# Modul_PCB_lama.net
KiCad netlist of a schematic drawn in EAGLE
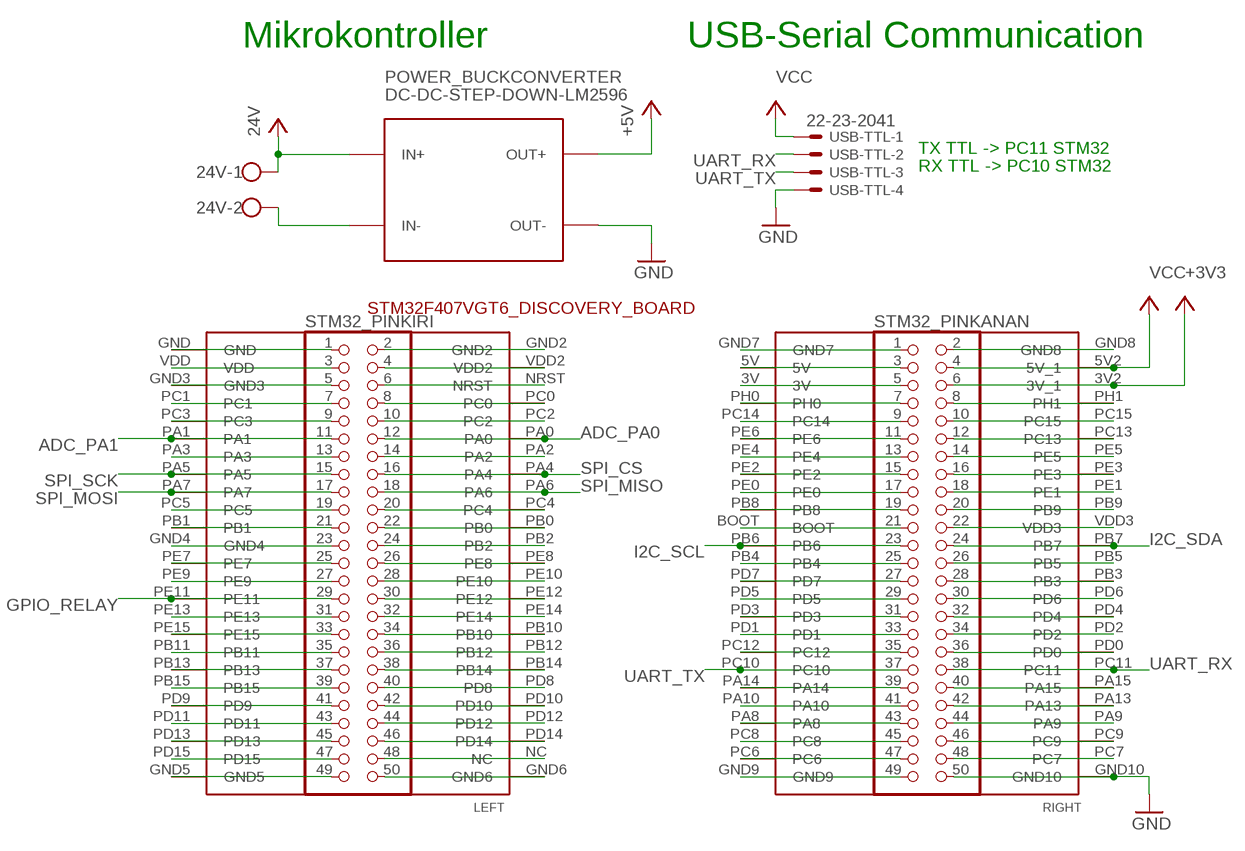
[diagram p0: schematic, sheet 1, part 1 of 2]
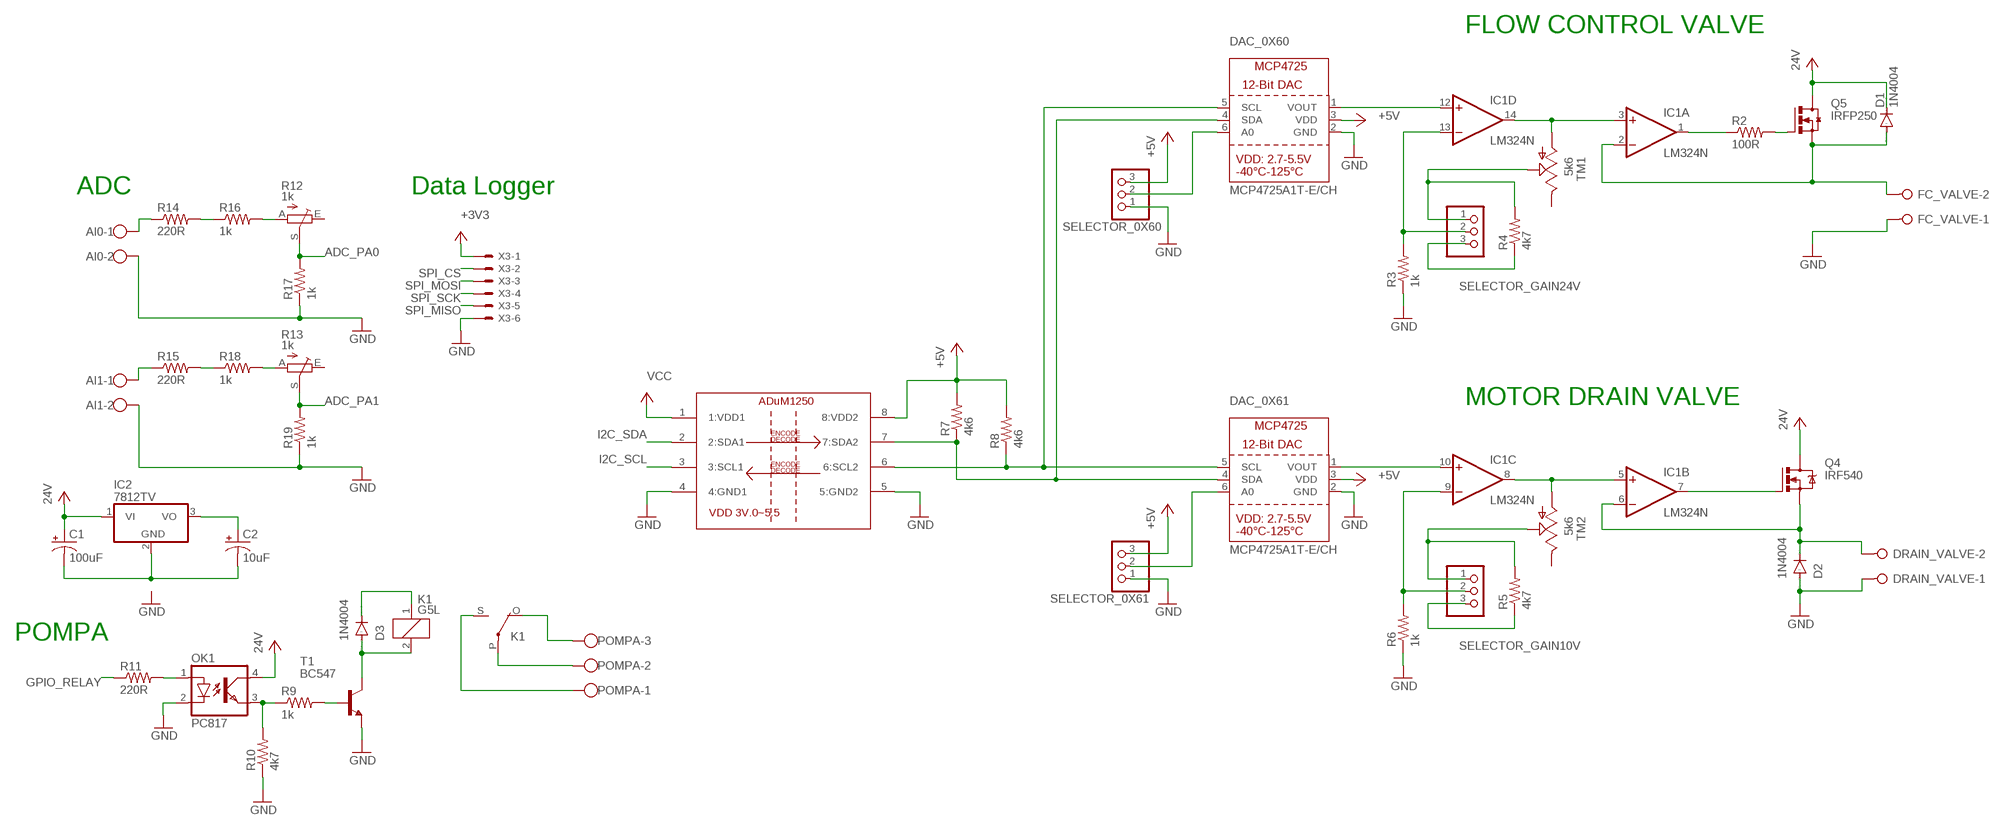
[diagram p1: schematic, sheet 1, part 2 of 2]

(export (version "E")
  (design (tool "Eeschema 10.0.6"))
  (components
    (comp (ref "24V")
      (value "W237-102")
      (footprint "eagle-import:W237-102")
      (fields (field (name "MPN") "237-102"))
      (libsource (lib "eagle-import") (part "W237-102"))
    )
    (comp (ref "AI0")
      (value "W237-102")
      (footprint "eagle-import:W237-102")
      (fields (field (name "MPN") "237-102"))
      (libsource (lib "eagle-import") (part "W237-102"))
    )
    (comp (ref "AI1")
      (value "W237-102")
      (footprint "eagle-import:W237-102")
      (fields (field (name "MPN") "237-102"))
      (libsource (lib "eagle-import") (part "W237-102"))
    )
    (comp (ref "C1")
      (value "100uF")
      (footprint "eagle-import:E2,5-6")
      (libsource (lib "eagle-import") (part "CPOL-USE2.5-6"))
    )
    (comp (ref "C2")
      (value "10uF")
      (footprint "eagle-import:E2,5-6")
      (libsource (lib "eagle-import") (part "CPOL-USE2.5-6"))
    )
    (comp (ref "D1")
      (value "1N4004")
      (footprint "eagle-import:DO41-10")
      (libsource (lib "eagle-import") (part "1N4004"))
    )
    (comp (ref "D2")
      (value "1N4004")
      (footprint "eagle-import:DO41-10")
      (libsource (lib "eagle-import") (part "1N4004"))
    )
    (comp (ref "D3")
      (value "1N4004")
      (footprint "eagle-import:DO41-10")
      (libsource (lib "eagle-import") (part "1N4004"))
    )
    (comp (ref "DAC_0X60")
      (value "MCP4725A1T-E/CH")
      (footprint "eagle-import:SOT23-6")
      (libsource (lib "eagle-import") (part "DAC_MCP4725"))
    )
    (comp (ref "DAC_0X61")
      (value "MCP4725A1T-E/CH")
      (footprint "eagle-import:SOT23-6")
      (libsource (lib "eagle-import") (part "DAC_MCP4725"))
    )
    (comp (ref "DRAIN_VALVE")
      (value "W237-02P")
      (footprint "eagle-import:W237-132")
      (libsource (lib "eagle-import") (part "W237-02P"))
    )
    (comp (ref "FC_VALVE")
      (value "W237-02P")
      (footprint "eagle-import:W237-132")
      (libsource (lib "eagle-import") (part "W237-02P"))
    )
    (comp (ref "IC1")
      (value "LM324N")
      (footprint "eagle-import:DIL14")
      (libsource (lib "eagle-import") (part "LM324N"))
    )
    (comp (ref "IC2")
      (value "7812TV")
      (footprint "eagle-import:TO220V")
      (libsource (lib "eagle-import") (part "78TV12"))
    )
    (comp (ref "K1")
      (value "G5L")
      (footprint "eagle-import:G5LE")
      (libsource (lib "eagle-import") (part "G5L"))
    )
    (comp (ref "OK1")
      (value "PC817")
      (footprint "eagle-import:DIL04")
      (fields (field (name "MPN") "PC817X4J000F"))
      (libsource (lib "eagle-import") (part "PC817"))
    )
    (comp (ref "POMPA")
      (value "W237-103")
      (footprint "eagle-import:W237-103")
      (fields (field (name "MPN") "237-103"))
      (libsource (lib "eagle-import") (part "W237-103"))
    )
    (comp (ref "POWER_BUCKCONVERTER")
      (value "DC-DC-STEP-DOWN-LM2596")
      (footprint "eagle-import:DC-DC-STEP-DOWN-LM2596")
      (libsource (lib "eagle-import") (part "DC-DC-STEP-DOWN-LM2596"))
    )
    (comp (ref "Q4")
      (value "IRF540")
      (footprint "eagle-import:TO220BV")
      (libsource (lib "eagle-import") (part "IRF540"))
    )
    (comp (ref "Q5")
      (value "IRFP250")
      (footprint "eagle-import:TO-247AD-V")
      (libsource (lib "eagle-import") (part "IRFP250"))
    )
    (comp (ref "R2")
      (value "100R")
      (footprint "eagle-import:0207_10")
      (libsource (lib "eagle-import") (part "R-US_0207/10"))
    )
    (comp (ref "R3")
      (value "1k")
      (footprint "eagle-import:0207_10")
      (libsource (lib "eagle-import") (part "R-US_0207/10"))
    )
    (comp (ref "R4")
      (value "4k7")
      (footprint "eagle-import:0207_10")
      (libsource (lib "eagle-import") (part "R-US_0207/10"))
    )
    (comp (ref "R5")
      (value "4k7")
      (footprint "eagle-import:0207_10")
      (libsource (lib "eagle-import") (part "R-US_0207/10"))
    )
    (comp (ref "R6")
      (value "1k")
      (footprint "eagle-import:0207_10")
      (libsource (lib "eagle-import") (part "R-US_0207/10"))
    )
    (comp (ref "R7")
      (value "4k6")
      (footprint "eagle-import:0207_10")
      (libsource (lib "eagle-import") (part "R-US_0207/10"))
    )
    (comp (ref "R8")
      (value "4k6")
      (footprint "eagle-import:0207_10")
      (libsource (lib "eagle-import") (part "R-US_0207/10"))
    )
    (comp (ref "R9")
      (value "1k")
      (footprint "eagle-import:0207_10")
      (libsource (lib "eagle-import") (part "R-US_0207/10"))
    )
    (comp (ref "R10")
      (value "4k7")
      (footprint "eagle-import:0207_10")
      (libsource (lib "eagle-import") (part "R-US_0207/10"))
    )
    (comp (ref "R11")
      (value "220R")
      (footprint "eagle-import:0207_10")
      (libsource (lib "eagle-import") (part "R-US_0207/10"))
    )
    (comp (ref "R12")
      (value "1k")
      (footprint "eagle-import:RJ9W")
      (libsource (lib "eagle-import") (part "TRIM_EU-RJ9W"))
    )
    (comp (ref "R13")
      (value "1k")
      (footprint "eagle-import:RJ9W")
      (libsource (lib "eagle-import") (part "TRIM_EU-RJ9W"))
    )
    (comp (ref "R14")
      (value "220R")
      (footprint "eagle-import:0207_10")
      (libsource (lib "eagle-import") (part "R-US_0207/10"))
    )
    (comp (ref "R15")
      (value "220R")
      (footprint "eagle-import:0207_10")
      (libsource (lib "eagle-import") (part "R-US_0207/10"))
    )
    (comp (ref "R16")
      (value "1k")
      (footprint "eagle-import:0207_10")
      (libsource (lib "eagle-import") (part "R-US_0207/10"))
    )
    (comp (ref "R17")
      (value "1k")
      (footprint "eagle-import:0207_10")
      (libsource (lib "eagle-import") (part "R-US_0207/10"))
    )
    (comp (ref "R18")
      (value "1k")
      (footprint "eagle-import:0207_10")
      (libsource (lib "eagle-import") (part "R-US_0207/10"))
    )
    (comp (ref "R19")
      (value "1k")
      (footprint "eagle-import:0207_10")
      (libsource (lib "eagle-import") (part "R-US_0207/10"))
    )
    (comp (ref "SELECTOR_0X60")
      (value "PINHD-1X3")
      (footprint "eagle-import:1X03")
      (libsource (lib "eagle-import") (part "PINHD-1X3"))
    )
    (comp (ref "SELECTOR_0X61")
      (value "PINHD-1X3")
      (footprint "eagle-import:1X03")
      (libsource (lib "eagle-import") (part "PINHD-1X3"))
    )
    (comp (ref "SELECTOR_GAIN10V")
      (value "PINHD-1X3")
      (footprint "eagle-import:1X03")
      (libsource (lib "eagle-import") (part "PINHD-1X3"))
    )
    (comp (ref "SELECTOR_GAIN24V")
      (value "PINHD-1X3")
      (footprint "eagle-import:1X03")
      (libsource (lib "eagle-import") (part "PINHD-1X3"))
    )
    (comp (ref "STM32F407VGT6_DISCOVERY_BOARD")
      (value "STM32F4-DISCOVERY")
      (footprint "eagle-import:STM32F407VG")
      (libsource (lib "eagle-import") (part "STM32F4-DISCOVERY"))
    )
    (comp (ref "STM32_PINKANAN")
      (value "PINHD-2X25")
      (footprint "eagle-import:2X25")
      (libsource (lib "eagle-import") (part "PINHD-2X25"))
    )
    (comp (ref "STM32_PINKIRI")
      (value "PINHD-2X25")
      (footprint "eagle-import:2X25")
      (libsource (lib "eagle-import") (part "PINHD-2X25"))
    )
    (comp (ref "T1")
      (value "BC547")
      (footprint "eagle-import:TO92")
      (libsource (lib "eagle-import") (part "BC547"))
    )
    (comp (ref "TM1")
      (value "5k6")
      (footprint "eagle-import:6MM")
      (libsource (lib "eagle-import") (part "TRIM"))
    )
    (comp (ref "TM2")
      (value "5k6")
      (footprint "eagle-import:6MM")
      (libsource (lib "eagle-import") (part "TRIM"))
    )
    (comp (ref "U$1")
      (value "ADUM1250")
      (footprint "eagle-import:SOIC_N")
      (libsource (lib "eagle-import") (part "ADUM1250"))
    )
    (comp (ref "USB-TTL")
      (value "22-23-2041")
      (footprint "eagle-import:22-23-2041")
      (fields (field (name "MF") "MOLEX"))
      (libsource (lib "eagle-import") (part "22-23-2041"))
    )
    (comp (ref "X3")
      (value "22-23-2061")
      (footprint "eagle-import:22-23-2061")
      (fields (field (name "MF") "MOLEX"))
      (libsource (lib "eagle-import") (part "22-23-2061"))
    )
  )
  (nets
    (net (code "1") (name "+3V3") (class "Default")
      (node (ref "STM32F407VGT6_DISCOVERY_BOARD") (pin "3V2") (pinfunction "3V_1_3V2") (pintype "bidirectional"))
      (node (ref "STM32_PINKANAN") (pin "6") (pinfunction "6_6") (pintype "passive"))
      (node (ref "X3") (pin "1") (pinfunction "S_1") (pintype "passive"))
    )
    (net (code "2") (name "+5V") (class "Default")
      (node (ref "DAC_0X60") (pin "3") (pinfunction "VDD_3") (pintype "power_in"))
      (node (ref "DAC_0X61") (pin "3") (pinfunction "VDD_3") (pintype "power_in"))
      (node (ref "POWER_BUCKCONVERTER") (pin "OUT+") (pinfunction "OUT+_OUT+") (pintype "bidirectional"))
      (node (ref "R7") (pin "2") (pinfunction "2_2") (pintype "passive"))
      (node (ref "R8") (pin "2") (pinfunction "2_2") (pintype "passive"))
      (node (ref "SELECTOR_0X60") (pin "3") (pinfunction "3_3") (pintype "passive"))
      (node (ref "SELECTOR_0X61") (pin "3") (pinfunction "3_3") (pintype "passive"))
      (node (ref "U$1") (pin "8") (pinfunction "8:VDD2_8") (pintype "bidirectional"))
    )
    (net (code "3") (name "/ADC_PA0") (class "Default")
      (node (ref "R12") (pin "S") (pinfunction "S_S") (pintype "passive"))
      (node (ref "R17") (pin "2") (pinfunction "2_2") (pintype "passive"))
      (node (ref "STM32F407VGT6_DISCOVERY_BOARD") (pin "PA0") (pinfunction "PA0_PA0") (pintype "bidirectional"))
      (node (ref "STM32_PINKIRI") (pin "12") (pinfunction "12_12") (pintype "passive"))
    )
    (net (code "4") (name "/ADC_PA1") (class "Default")
      (node (ref "R13") (pin "S") (pinfunction "S_S") (pintype "passive"))
      (node (ref "R19") (pin "2") (pinfunction "2_2") (pintype "passive"))
      (node (ref "STM32F407VGT6_DISCOVERY_BOARD") (pin "PA1") (pinfunction "PA1_PA1") (pintype "bidirectional"))
      (node (ref "STM32_PINKIRI") (pin "11") (pinfunction "11_11") (pintype "passive"))
    )
    (net (code "5") (name "/GPIO_RELAY") (class "Default")
      (node (ref "R11") (pin "1") (pinfunction "1_1") (pintype "passive"))
      (node (ref "STM32F407VGT6_DISCOVERY_BOARD") (pin "PE11") (pinfunction "PE11_PE11") (pintype "bidirectional"))
      (node (ref "STM32_PINKIRI") (pin "29") (pinfunction "29_29") (pintype "passive"))
    )
    (net (code "6") (name "/I2C_SCL") (class "Default")
      (node (ref "STM32F407VGT6_DISCOVERY_BOARD") (pin "PB6") (pinfunction "PB6_PB6") (pintype "bidirectional"))
      (node (ref "STM32_PINKANAN") (pin "23") (pinfunction "23_23") (pintype "passive"))
      (node (ref "U$1") (pin "3") (pinfunction "3:SCL1_3") (pintype "bidirectional"))
    )
    (net (code "7") (name "/I2C_SDA") (class "Default")
      (node (ref "STM32F407VGT6_DISCOVERY_BOARD") (pin "PB7") (pinfunction "PB7_PB7") (pintype "bidirectional"))
      (node (ref "STM32_PINKANAN") (pin "24") (pinfunction "24_24") (pintype "passive"))
      (node (ref "U$1") (pin "2") (pinfunction "2:SDA1_2") (pintype "bidirectional"))
    )
    (net (code "8") (name "/SPI_CS") (class "Default")
      (node (ref "STM32F407VGT6_DISCOVERY_BOARD") (pin "PA4") (pinfunction "PA4_PA4") (pintype "bidirectional"))
      (node (ref "STM32_PINKIRI") (pin "16") (pinfunction "16_16") (pintype "passive"))
      (node (ref "X3") (pin "2") (pinfunction "S_2") (pintype "passive"))
    )
    (net (code "9") (name "/SPI_MISO") (class "Default")
      (node (ref "STM32F407VGT6_DISCOVERY_BOARD") (pin "PA6") (pinfunction "PA6_PA6") (pintype "bidirectional"))
      (node (ref "STM32_PINKIRI") (pin "18") (pinfunction "18_18") (pintype "passive"))
      (node (ref "X3") (pin "5") (pinfunction "S_5") (pintype "passive"))
    )
    (net (code "10") (name "/SPI_MOSI") (class "Default")
      (node (ref "STM32F407VGT6_DISCOVERY_BOARD") (pin "PA7") (pinfunction "PA7_PA7") (pintype "bidirectional"))
      (node (ref "STM32_PINKIRI") (pin "17") (pinfunction "17_17") (pintype "passive"))
      (node (ref "X3") (pin "3") (pinfunction "S_3") (pintype "passive"))
    )
    (net (code "11") (name "/SPI_SCK") (class "Default")
      (node (ref "STM32F407VGT6_DISCOVERY_BOARD") (pin "PA5") (pinfunction "PA5_PA5") (pintype "bidirectional"))
      (node (ref "STM32_PINKIRI") (pin "15") (pinfunction "15_15") (pintype "passive"))
      (node (ref "X3") (pin "4") (pinfunction "S_4") (pintype "passive"))
    )
    (net (code "12") (name "/UART_RX") (class "Default")
      (node (ref "STM32F407VGT6_DISCOVERY_BOARD") (pin "PC11") (pinfunction "PC11_PC11") (pintype "bidirectional"))
      (node (ref "STM32_PINKANAN") (pin "38") (pinfunction "38_38") (pintype "passive"))
      (node (ref "USB-TTL") (pin "2") (pinfunction "S_2") (pintype "passive"))
    )
    (net (code "13") (name "/UART_TX") (class "Default")
      (node (ref "STM32F407VGT6_DISCOVERY_BOARD") (pin "PC10") (pinfunction "PC10_PC10") (pintype "bidirectional"))
      (node (ref "STM32_PINKANAN") (pin "37") (pinfunction "37_37") (pintype "passive"))
      (node (ref "USB-TTL") (pin "3") (pinfunction "S_3") (pintype "passive"))
    )
    (net (code "14") (name "24V") (class "Default")
      (node (ref "24V") (pin "1") (pinfunction "KL_1") (pintype "passive"))
      (node (ref "C1") (pin "+") (pinfunction "+_+") (pintype "passive"))
      (node (ref "D1") (pin "C") (pinfunction "C_C") (pintype "passive"))
      (node (ref "IC2") (pin "1") (pinfunction "VI_1") (pintype "input"))
      (node (ref "OK1") (pin "4") (pinfunction "COL_4") (pintype "passive"))
      (node (ref "POWER_BUCKCONVERTER") (pin "IN+") (pinfunction "IN+_IN+") (pintype "bidirectional"))
      (node (ref "Q4") (pin "D") (pinfunction "D_D") (pintype "passive"))
      (node (ref "Q5") (pin "D") (pinfunction "D_D") (pintype "passive"))
      (node (ref "STM32F407VGT6_DISCOVERY_BOARD") (pin "5V2") (pinfunction "5V_1_5V2") (pintype "bidirectional"))
      (node (ref "STM32_PINKANAN") (pin "4") (pinfunction "4_4") (pintype "passive"))
      (node (ref "U$1") (pin "1") (pinfunction "1:VDD1_1") (pintype "bidirectional"))
      (node (ref "USB-TTL") (pin "1") (pinfunction "S_1") (pintype "passive"))
    )
    (net (code "15") (name "GND") (class "Default")
      (node (ref "AI0") (pin "2") (pinfunction "KL_2") (pintype "passive"))
      (node (ref "AI1") (pin "2") (pinfunction "KL_2") (pintype "passive"))
      (node (ref "D2") (pin "A") (pinfunction "A_A") (pintype "passive"))
      (node (ref "DAC_0X60") (pin "2") (pinfunction "GND_2") (pintype "power_in"))
      (node (ref "DAC_0X61") (pin "2") (pinfunction "GND_2") (pintype "power_in"))
      (node (ref "DRAIN_VALVE") (pin "1") (pinfunction "KL_1") (pintype "passive"))
      (node (ref "FC_VALVE") (pin "1") (pinfunction "KL_1") (pintype "passive"))
      (node (ref "OK1") (pin "2") (pinfunction "C_2") (pintype "passive"))
      (node (ref "POWER_BUCKCONVERTER") (pin "OUT-") (pinfunction "OUT-_OUT-") (pintype "bidirectional"))
      (node (ref "R10") (pin "1") (pinfunction "1_1") (pintype "passive"))
      (node (ref "R17") (pin "1") (pinfunction "1_1") (pintype "passive"))
      (node (ref "R19") (pin "1") (pinfunction "1_1") (pintype "passive"))
      (node (ref "R3") (pin "1") (pinfunction "1_1") (pintype "passive"))
      (node (ref "R6") (pin "1") (pinfunction "1_1") (pintype "passive"))
      (node (ref "SELECTOR_0X60") (pin "1") (pinfunction "1_1") (pintype "passive"))
      (node (ref "SELECTOR_0X61") (pin "1") (pinfunction "1_1") (pintype "passive"))
      (node (ref "STM32F407VGT6_DISCOVERY_BOARD") (pin "GND10") (pinfunction "GND10_GND10") (pintype "bidirectional"))
      (node (ref "STM32_PINKANAN") (pin "50") (pinfunction "50_50") (pintype "passive"))
      (node (ref "T1") (pin "1") (pinfunction "E_1") (pintype "passive"))
      (node (ref "U$1") (pin "4") (pinfunction "4:GND1_4") (pintype "bidirectional"))
      (node (ref "U$1") (pin "5") (pinfunction "5:GND2_5") (pintype "bidirectional"))
      (node (ref "USB-TTL") (pin "4") (pinfunction "S_4") (pintype "passive"))
      (node (ref "X3") (pin "6") (pinfunction "S_6") (pintype "passive"))
    )
    (net (code "16") (name "Net-(24VB-KL)") (class "Default")
      (node (ref "24V") (pin "2") (pinfunction "KL_2") (pintype "passive"))
      (node (ref "POWER_BUCKCONVERTER") (pin "IN-") (pinfunction "IN-_IN-") (pintype "bidirectional"))
    )
    (net (code "17") (name "Net-(AI0A-KL)") (class "Default")
      (node (ref "AI0") (pin "1") (pinfunction "KL_1") (pintype "passive"))
      (node (ref "R14") (pin "1") (pinfunction "1_1") (pintype "passive"))
    )
    (net (code "18") (name "Net-(AI1A-KL)") (class "Default")
      (node (ref "AI1") (pin "1") (pinfunction "KL_1") (pintype "passive"))
      (node (ref "R15") (pin "1") (pinfunction "1_1") (pintype "passive"))
    )
    (net (code "19") (name "Net-(D3-PadC)") (class "Default")
      (node (ref "D3") (pin "C") (pinfunction "C_C") (pintype "passive"))
      (node (ref "K1") (pin "1") (pinfunction "1_1") (pintype "passive"))
    )
    (net (code "20") (name "Net-(DAC_0X60-A0)") (class "Default")
      (node (ref "DAC_0X60") (pin "6") (pinfunction "A0_6") (pintype "input"))
      (node (ref "SELECTOR_0X60") (pin "2") (pinfunction "2_2") (pintype "passive"))
    )
    (net (code "21") (name "Net-(DAC_0X60-SCL)") (class "Default")
      (node (ref "DAC_0X60") (pin "5") (pinfunction "SCL_5") (pintype "bidirectional"))
      (node (ref "DAC_0X61") (pin "5") (pinfunction "SCL_5") (pintype "bidirectional"))
      (node (ref "R8") (pin "1") (pinfunction "1_1") (pintype "passive"))
      (node (ref "U$1") (pin "6") (pinfunction "6:SCL2_6") (pintype "bidirectional"))
    )
    (net (code "22") (name "Net-(DAC_0X60-SDA)") (class "Default")
      (node (ref "DAC_0X60") (pin "4") (pinfunction "SDA_4") (pintype "bidirectional"))
      (node (ref "DAC_0X61") (pin "4") (pinfunction "SDA_4") (pintype "bidirectional"))
      (node (ref "R7") (pin "1") (pinfunction "1_1") (pintype "passive"))
      (node (ref "U$1") (pin "7") (pinfunction "7:SDA2_7") (pintype "bidirectional"))
    )
    (net (code "23") (name "Net-(DAC_0X60-VOUT)") (class "Default")
      (node (ref "DAC_0X60") (pin "1") (pinfunction "VOUT_1") (pintype "output"))
      (node (ref "IC1") (pin "12") (pinfunction "+IN_12") (pintype "input"))
    )
    (net (code "24") (name "Net-(DAC_0X61-A0)") (class "Default")
      (node (ref "DAC_0X61") (pin "6") (pinfunction "A0_6") (pintype "input"))
      (node (ref "SELECTOR_0X61") (pin "2") (pinfunction "2_2") (pintype "passive"))
    )
    (net (code "25") (name "Net-(DAC_0X61-VOUT)") (class "Default")
      (node (ref "DAC_0X61") (pin "1") (pinfunction "VOUT_1") (pintype "output"))
      (node (ref "IC1") (pin "10") (pinfunction "+IN_10") (pintype "input"))
    )
    (net (code "26") (name "Net-(DRAIN_VALVEB-KL)") (class "Default")
      (node (ref "D2") (pin "C") (pinfunction "C_C") (pintype "passive"))
      (node (ref "DRAIN_VALVE") (pin "2") (pinfunction "KL_2") (pintype "passive"))
      (node (ref "IC1") (pin "6") (pinfunction "-IN_6") (pintype "input"))
      (node (ref "Q4") (pin "S") (pinfunction "S_S") (pintype "passive"))
    )
    (net (code "27") (name "Net-(FC_VALVEB-KL)") (class "Default")
      (node (ref "D1") (pin "A") (pinfunction "A_A") (pintype "passive"))
      (node (ref "FC_VALVE") (pin "2") (pinfunction "KL_2") (pintype "passive"))
      (node (ref "IC1") (pin "2") (pinfunction "-IN_2") (pintype "input"))
      (node (ref "Q5") (pin "S") (pinfunction "S_S") (pintype "passive"))
    )
    (net (code "28") (name "Net-(IC1A-+IN)") (class "Default")
      (node (ref "IC1") (pin "14") (pinfunction "OUT_14") (pintype "output"))
      (node (ref "IC1") (pin "3") (pinfunction "+IN_3") (pintype "input"))
      (node (ref "TM1") (pin "A") (pinfunction "A_A") (pintype "passive"))
    )
    (net (code "29") (name "Net-(IC1A-OUT)") (class "Default")
      (node (ref "IC1") (pin "1") (pinfunction "OUT_1") (pintype "output"))
      (node (ref "R2") (pin "1") (pinfunction "1_1") (pintype "passive"))
    )
    (net (code "30") (name "Net-(IC1B-+IN)") (class "Default")
      (node (ref "IC1") (pin "5") (pinfunction "+IN_5") (pintype "input"))
      (node (ref "IC1") (pin "8") (pinfunction "OUT_8") (pintype "output"))
      (node (ref "TM2") (pin "A") (pinfunction "A_A") (pintype "passive"))
    )
    (net (code "31") (name "Net-(IC1B-OUT)") (class "Default")
      (node (ref "IC1") (pin "7") (pinfunction "OUT_7") (pintype "output"))
      (node (ref "Q4") (pin "G") (pinfunction "G_G") (pintype "passive"))
    )
    (net (code "32") (name "Net-(IC1C--IN)") (class "Default")
      (node (ref "IC1") (pin "9") (pinfunction "-IN_9") (pintype "input"))
      (node (ref "R6") (pin "2") (pinfunction "2_2") (pintype "passive"))
      (node (ref "SELECTOR_GAIN10V") (pin "2") (pinfunction "2_2") (pintype "passive"))
    )
    (net (code "33") (name "Net-(IC1D--IN)") (class "Default")
      (node (ref "IC1") (pin "13") (pinfunction "-IN_13") (pintype "input"))
      (node (ref "R3") (pin "2") (pinfunction "2_2") (pintype "passive"))
      (node (ref "SELECTOR_GAIN24V") (pin "2") (pinfunction "2_2") (pintype "passive"))
    )
    (net (code "34") (name "Net-(IC2-GND)") (class "Default")
      (node (ref "C1") (pin "-") (pinfunction "-_-") (pintype "passive"))
      (node (ref "C2") (pin "-") (pinfunction "-_-") (pintype "passive"))
      (node (ref "IC2") (pin "2") (pinfunction "GND_2") (pintype "passive"))
    )
    (net (code "35") (name "Net-(IC2-VO)") (class "Default")
      (node (ref "C2") (pin "+") (pinfunction "+_+") (pintype "passive"))
      (node (ref "IC2") (pin "3") (pinfunction "VO_3") (pintype "passive"))
    )
    (net (code "36") (name "Net-(OK1-A)") (class "Default")
      (node (ref "OK1") (pin "1") (pinfunction "A_1") (pintype "passive"))
      (node (ref "R11") (pin "2") (pinfunction "2_2") (pintype "passive"))
    )
    (net (code "37") (name "Net-(OK1-EMIT)") (class "Default")
      (node (ref "OK1") (pin "3") (pinfunction "EMIT_3") (pintype "passive"))
      (node (ref "R10") (pin "2") (pinfunction "2_2") (pintype "passive"))
      (node (ref "R9") (pin "1") (pinfunction "1_1") (pintype "passive"))
    )
    (net (code "38") (name "Net-(POMPAA-KL)") (class "Default")
      (node (ref "K1") (pin "S") (pinfunction "S_S") (pintype "passive"))
      (node (ref "POMPA") (pin "1") (pinfunction "KL_1") (pintype "passive"))
    )
    (net (code "39") (name "Net-(POMPAB-KL)") (class "Default")
      (node (ref "K1") (pin "P") (pinfunction "P_P") (pintype "passive"))
      (node (ref "POMPA") (pin "2") (pinfunction "KL_2") (pintype "passive"))
    )
    (net (code "40") (name "Net-(POMPAC-KL)") (class "Default")
      (node (ref "K1") (pin "O") (pinfunction "O_O") (pintype "passive"))
      (node (ref "POMPA") (pin "3") (pinfunction "KL_3") (pintype "passive"))
    )
    (net (code "41") (name "Net-(Q5-PadG)") (class "Default")
      (node (ref "Q5") (pin "G") (pinfunction "G_G") (pintype "passive"))
      (node (ref "R2") (pin "2") (pinfunction "2_2") (pintype "passive"))
    )
    (net (code "42") (name "Net-(R4-Pad1)") (class "Default")
      (node (ref "R4") (pin "1") (pinfunction "1_1") (pintype "passive"))
      (node (ref "SELECTOR_GAIN24V") (pin "3") (pinfunction "3_3") (pintype "passive"))
    )
    (net (code "43") (name "Net-(R4-Pad2)") (class "Default")
      (node (ref "R4") (pin "2") (pinfunction "2_2") (pintype "passive"))
      (node (ref "SELECTOR_GAIN24V") (pin "1") (pinfunction "1_1") (pintype "passive"))
      (node (ref "TM1") (pin "S") (pinfunction "S_S") (pintype "passive"))
    )
    (net (code "44") (name "Net-(R5-Pad1)") (class "Default")
      (node (ref "R5") (pin "1") (pinfunction "1_1") (pintype "passive"))
      (node (ref "SELECTOR_GAIN10V") (pin "3") (pinfunction "3_3") (pintype "passive"))
    )
    (net (code "45") (name "Net-(R5-Pad2)") (class "Default")
      (node (ref "R5") (pin "2") (pinfunction "2_2") (pintype "passive"))
      (node (ref "SELECTOR_GAIN10V") (pin "1") (pinfunction "1_1") (pintype "passive"))
      (node (ref "TM2") (pin "S") (pinfunction "S_S") (pintype "passive"))
    )
    (net (code "46") (name "Net-(R12-PadA)") (class "Default")
      (node (ref "R12") (pin "A") (pinfunction "A_A") (pintype "passive"))
      (node (ref "R16") (pin "2") (pinfunction "2_2") (pintype "passive"))
    )
    (net (code "47") (name "Net-(R13-PadA)") (class "Default")
      (node (ref "R13") (pin "A") (pinfunction "A_A") (pintype "passive"))
      (node (ref "R18") (pin "2") (pinfunction "2_2") (pintype "passive"))
    )
    (net (code "48") (name "Net-(R14-Pad2)") (class "Default")
      (node (ref "R14") (pin "2") (pinfunction "2_2") (pintype "passive"))
      (node (ref "R16") (pin "1") (pinfunction "1_1") (pintype "passive"))
    )
    (net (code "49") (name "Net-(R15-Pad2)") (class "Default")
      (node (ref "R15") (pin "2") (pinfunction "2_2") (pintype "passive"))
      (node (ref "R18") (pin "1") (pinfunction "1_1") (pintype "passive"))
    )
    (net (code "50") (name "Net-(STM32F407VGT6_DISCOVERY_BOARD-Pad3V)") (class "Default")
      (node (ref "STM32F407VGT6_DISCOVERY_BOARD") (pin "3V") (pinfunction "3V_3V") (pintype "bidirectional"))
      (node (ref "STM32_PINKANAN") (pin "5") (pinfunction "5_5") (pintype "passive"))
    )
    (net (code "51") (name "Net-(STM32F407VGT6_DISCOVERY_BOARD-Pad5V)") (class "Default")
      (node (ref "STM32F407VGT6_DISCOVERY_BOARD") (pin "5V") (pinfunction "5V_5V") (pintype "bidirectional"))
      (node (ref "STM32_PINKANAN") (pin "3") (pinfunction "3_3") (pintype "passive"))
    )
    (net (code "52") (name "Net-(STM32F407VGT6_DISCOVERY_BOARD-PadBOOT)") (class "Default")
      (node (ref "STM32F407VGT6_DISCOVERY_BOARD") (pin "BOOT") (pinfunction "BOOT_BOOT") (pintype "bidirectional"))
      (node (ref "STM32_PINKANAN") (pin "21") (pinfunction "21_21") (pintype "passive"))
    )
    (net (code "53") (name "Net-(STM32F407VGT6_DISCOVERY_BOARD-PadGND)") (class "Default")
      (node (ref "STM32F407VGT6_DISCOVERY_BOARD") (pin "GND") (pinfunction "GND_GND") (pintype "bidirectional"))
      (node (ref "STM32_PINKIRI") (pin "1") (pinfunction "1_1") (pintype "passive"))
    )
    (net (code "54") (name "Net-(STM32F407VGT6_DISCOVERY_BOARD-PadGND2)") (class "Default")
      (node (ref "STM32F407VGT6_DISCOVERY_BOARD") (pin "GND2") (pinfunction "GND2_GND2") (pintype "bidirectional"))
      (node (ref "STM32_PINKIRI") (pin "2") (pinfunction "2_2") (pintype "passive"))
    )
    (net (code "55") (name "Net-(STM32F407VGT6_DISCOVERY_BOARD-PadGND3)") (class "Default")
      (node (ref "STM32F407VGT6_DISCOVERY_BOARD") (pin "GND3") (pinfunction "GND3_GND3") (pintype "bidirectional"))
      (node (ref "STM32_PINKIRI") (pin "5") (pinfunction "5_5") (pintype "passive"))
    )
    (net (code "56") (name "Net-(STM32F407VGT6_DISCOVERY_BOARD-PadGND4)") (class "Default")
      (node (ref "STM32F407VGT6_DISCOVERY_BOARD") (pin "GND4") (pinfunction "GND4_GND4") (pintype "bidirectional"))
      (node (ref "STM32_PINKIRI") (pin "23") (pinfunction "23_23") (pintype "passive"))
    )
    (net (code "57") (name "Net-(STM32F407VGT6_DISCOVERY_BOARD-PadGND5)") (class "Default")
      (node (ref "STM32F407VGT6_DISCOVERY_BOARD") (pin "GND5") (pinfunction "GND5_GND5") (pintype "bidirectional"))
      (node (ref "STM32_PINKIRI") (pin "49") (pinfunction "49_49") (pintype "passive"))
    )
    (net (code "58") (name "Net-(STM32F407VGT6_DISCOVERY_BOARD-PadGND6)") (class "Default")
      (node (ref "STM32F407VGT6_DISCOVERY_BOARD") (pin "GND6") (pinfunction "GND6_GND6") (pintype "bidirectional"))
      (node (ref "STM32_PINKIRI") (pin "50") (pinfunction "50_50") (pintype "passive"))
    )
    (net (code "59") (name "Net-(STM32F407VGT6_DISCOVERY_BOARD-PadGND7)") (class "Default")
      (node (ref "STM32F407VGT6_DISCOVERY_BOARD") (pin "GND7") (pinfunction "GND7_GND7") (pintype "bidirectional"))
      (node (ref "STM32_PINKANAN") (pin "1") (pinfunction "1_1") (pintype "passive"))
    )
    (net (code "60") (name "Net-(STM32F407VGT6_DISCOVERY_BOARD-PadGND8)") (class "Default")
      (node (ref "STM32F407VGT6_DISCOVERY_BOARD") (pin "GND8") (pinfunction "GND8_GND8") (pintype "bidirectional"))
      (node (ref "STM32_PINKANAN") (pin "2") (pinfunction "2_2") (pintype "passive"))
    )
    (net (code "61") (name "Net-(STM32F407VGT6_DISCOVERY_BOARD-PadGND9)") (class "Default")
      (node (ref "STM32F407VGT6_DISCOVERY_BOARD") (pin "GND9") (pinfunction "GND9_GND9") (pintype "bidirectional"))
      (node (ref "STM32_PINKANAN") (pin "49") (pinfunction "49_49") (pintype "passive"))
    )
    (net (code "62") (name "Net-(STM32F407VGT6_DISCOVERY_BOARD-PadNC)") (class "Default")
      (node (ref "STM32F407VGT6_DISCOVERY_BOARD") (pin "NC") (pinfunction "NC_NC") (pintype "bidirectional"))
      (node (ref "STM32_PINKIRI") (pin "48") (pinfunction "48_48") (pintype "passive"))
    )
    (net (code "63") (name "Net-(STM32F407VGT6_DISCOVERY_BOARD-PadNRST)") (class "Default")
      (node (ref "STM32F407VGT6_DISCOVERY_BOARD") (pin "NRST") (pinfunction "NRST_NRST") (pintype "bidirectional"))
      (node (ref "STM32_PINKIRI") (pin "6") (pinfunction "6_6") (pintype "passive"))
    )
    (net (code "64") (name "Net-(STM32F407VGT6_DISCOVERY_BOARD-PadPA2)") (class "Default")
      (node (ref "STM32F407VGT6_DISCOVERY_BOARD") (pin "PA2") (pinfunction "PA2_PA2") (pintype "bidirectional"))
      (node (ref "STM32_PINKIRI") (pin "14") (pinfunction "14_14") (pintype "passive"))
    )
    (net (code "65") (name "Net-(STM32F407VGT6_DISCOVERY_BOARD-PadPA3)") (class "Default")
      (node (ref "STM32F407VGT6_DISCOVERY_BOARD") (pin "PA3") (pinfunction "PA3_PA3") (pintype "bidirectional"))
      (node (ref "STM32_PINKIRI") (pin "13") (pinfunction "13_13") (pintype "passive"))
    )
    (net (code "66") (name "Net-(STM32F407VGT6_DISCOVERY_BOARD-PadPA8)") (class "Default")
      (node (ref "STM32F407VGT6_DISCOVERY_BOARD") (pin "PA8") (pinfunction "PA8_PA8") (pintype "bidirectional"))
      (node (ref "STM32_PINKANAN") (pin "43") (pinfunction "43_43") (pintype "passive"))
    )
    (net (code "67") (name "Net-(STM32F407VGT6_DISCOVERY_BOARD-PadPA9)") (class "Default")
      (node (ref "STM32F407VGT6_DISCOVERY_BOARD") (pin "PA9") (pinfunction "PA9_PA9") (pintype "bidirectional"))
      (node (ref "STM32_PINKANAN") (pin "44") (pinfunction "44_44") (pintype "passive"))
    )
    (net (code "68") (name "Net-(STM32F407VGT6_DISCOVERY_BOARD-PadPA10)") (class "Default")
      (node (ref "STM32F407VGT6_DISCOVERY_BOARD") (pin "PA10") (pinfunction "PA10_PA10") (pintype "bidirectional"))
      (node (ref "STM32_PINKANAN") (pin "41") (pinfunction "41_41") (pintype "passive"))
    )
    (net (code "69") (name "Net-(STM32F407VGT6_DISCOVERY_BOARD-PadPA13)") (class "Default")
      (node (ref "STM32F407VGT6_DISCOVERY_BOARD") (pin "PA13") (pinfunction "PA13_PA13") (pintype "bidirectional"))
      (node (ref "STM32_PINKANAN") (pin "42") (pinfunction "42_42") (pintype "passive"))
    )
    (net (code "70") (name "Net-(STM32F407VGT6_DISCOVERY_BOARD-PadPA14)") (class "Default")
      (node (ref "STM32F407VGT6_DISCOVERY_BOARD") (pin "PA14") (pinfunction "PA14_PA14") (pintype "bidirectional"))
      (node (ref "STM32_PINKANAN") (pin "39") (pinfunction "39_39") (pintype "passive"))
    )
    (net (code "71") (name "Net-(STM32F407VGT6_DISCOVERY_BOARD-PadPA15)") (class "Default")
      (node (ref "STM32F407VGT6_DISCOVERY_BOARD") (pin "PA15") (pinfunction "PA15_PA15") (pintype "bidirectional"))
      (node (ref "STM32_PINKANAN") (pin "40") (pinfunction "40_40") (pintype "passive"))
    )
    (net (code "72") (name "Net-(STM32F407VGT6_DISCOVERY_BOARD-PadPB0)") (class "Default")
      (node (ref "STM32F407VGT6_DISCOVERY_BOARD") (pin "PB0") (pinfunction "PB0_PB0") (pintype "bidirectional"))
      (node (ref "STM32_PINKIRI") (pin "22") (pinfunction "22_22") (pintype "passive"))
    )
    (net (code "73") (name "Net-(STM32F407VGT6_DISCOVERY_BOARD-PadPB1)") (class "Default")
      (node (ref "STM32F407VGT6_DISCOVERY_BOARD") (pin "PB1") (pinfunction "PB1_PB1") (pintype "bidirectional"))
      (node (ref "STM32_PINKIRI") (pin "21") (pinfunction "21_21") (pintype "passive"))
    )
    (net (code "74") (name "Net-(STM32F407VGT6_DISCOVERY_BOARD-PadPB2)") (class "Default")
      (node (ref "STM32F407VGT6_DISCOVERY_BOARD") (pin "PB2") (pinfunction "PB2_PB2") (pintype "bidirectional"))
      (node (ref "STM32_PINKIRI") (pin "24") (pinfunction "24_24") (pintype "passive"))
    )
    (net (code "75") (name "Net-(STM32F407VGT6_DISCOVERY_BOARD-PadPB3)") (class "Default")
      (node (ref "STM32F407VGT6_DISCOVERY_BOARD") (pin "PB3") (pinfunction "PB3_PB3") (pintype "bidirectional"))
      (node (ref "STM32_PINKANAN") (pin "28") (pinfunction "28_28") (pintype "passive"))
    )
    (net (code "76") (name "Net-(STM32F407VGT6_DISCOVERY_BOARD-PadPB4)") (class "Default")
      (node (ref "STM32F407VGT6_DISCOVERY_BOARD") (pin "PB4") (pinfunction "PB4_PB4") (pintype "bidirectional"))
      (node (ref "STM32_PINKANAN") (pin "25") (pinfunction "25_25") (pintype "passive"))
    )
    (net (code "77") (name "Net-(STM32F407VGT6_DISCOVERY_BOARD-PadPB5)") (class "Default")
      (node (ref "STM32F407VGT6_DISCOVERY_BOARD") (pin "PB5") (pinfunction "PB5_PB5") (pintype "bidirectional"))
      (node (ref "STM32_PINKANAN") (pin "26") (pinfunction "26_26") (pintype "passive"))
    )
    (net (code "78") (name "Net-(STM32F407VGT6_DISCOVERY_BOARD-PadPB8)") (class "Default")
      (node (ref "STM32F407VGT6_DISCOVERY_BOARD") (pin "PB8") (pinfunction "PB8_PB8") (pintype "bidirectional"))
      (node (ref "STM32_PINKANAN") (pin "19") (pinfunction "19_19") (pintype "passive"))
    )
    (net (code "79") (name "Net-(STM32F407VGT6_DISCOVERY_BOARD-PadPB9)") (class "Default")
      (node (ref "STM32F407VGT6_DISCOVERY_BOARD") (pin "PB9") (pinfunction "PB9_PB9") (pintype "bidirectional"))
      (node (ref "STM32_PINKANAN") (pin "20") (pinfunction "20_20") (pintype "passive"))
    )
    (net (code "80") (name "Net-(STM32F407VGT6_DISCOVERY_BOARD-PadPB10)") (class "Default")
      (node (ref "STM32F407VGT6_DISCOVERY_BOARD") (pin "PB10") (pinfunction "PB10_PB10") (pintype "bidirectional"))
      (node (ref "STM32_PINKIRI") (pin "34") (pinfunction "34_34") (pintype "passive"))
    )
    (net (code "81") (name "Net-(STM32F407VGT6_DISCOVERY_BOARD-PadPB11)") (class "Default")
      (node (ref "STM32F407VGT6_DISCOVERY_BOARD") (pin "PB11") (pinfunction "PB11_PB11") (pintype "bidirectional"))
      (node (ref "STM32_PINKIRI") (pin "35") (pinfunction "35_35") (pintype "passive"))
    )
    (net (code "82") (name "Net-(STM32F407VGT6_DISCOVERY_BOARD-PadPB12)") (class "Default")
      (node (ref "STM32F407VGT6_DISCOVERY_BOARD") (pin "PB12") (pinfunction "PB12_PB12") (pintype "bidirectional"))
      (node (ref "STM32_PINKIRI") (pin "36") (pinfunction "36_36") (pintype "passive"))
    )
    (net (code "83") (name "Net-(STM32F407VGT6_DISCOVERY_BOARD-PadPB13)") (class "Default")
      (node (ref "STM32F407VGT6_DISCOVERY_BOARD") (pin "PB13") (pinfunction "PB13_PB13") (pintype "bidirectional"))
      (node (ref "STM32_PINKIRI") (pin "37") (pinfunction "37_37") (pintype "passive"))
    )
    (net (code "84") (name "Net-(STM32F407VGT6_DISCOVERY_BOARD-PadPB14)") (class "Default")
      (node (ref "STM32F407VGT6_DISCOVERY_BOARD") (pin "PB14") (pinfunction "PB14_PB14") (pintype "bidirectional"))
      (node (ref "STM32_PINKIRI") (pin "38") (pinfunction "38_38") (pintype "passive"))
    )
    (net (code "85") (name "Net-(STM32F407VGT6_DISCOVERY_BOARD-PadPB15)") (class "Default")
      (node (ref "STM32F407VGT6_DISCOVERY_BOARD") (pin "PB15") (pinfunction "PB15_PB15") (pintype "bidirectional"))
      (node (ref "STM32_PINKIRI") (pin "39") (pinfunction "39_39") (pintype "passive"))
    )
    (net (code "86") (name "Net-(STM32F407VGT6_DISCOVERY_BOARD-PadPC0)") (class "Default")
      (node (ref "STM32F407VGT6_DISCOVERY_BOARD") (pin "PC0") (pinfunction "PC0_PC0") (pintype "bidirectional"))
      (node (ref "STM32_PINKIRI") (pin "8") (pinfunction "8_8") (pintype "passive"))
    )
    (net (code "87") (name "Net-(STM32F407VGT6_DISCOVERY_BOARD-PadPC1)") (class "Default")
      (node (ref "STM32F407VGT6_DISCOVERY_BOARD") (pin "PC1") (pinfunction "PC1_PC1") (pintype "bidirectional"))
      (node (ref "STM32_PINKIRI") (pin "7") (pinfunction "7_7") (pintype "passive"))
    )
    (net (code "88") (name "Net-(STM32F407VGT6_DISCOVERY_BOARD-PadPC2)") (class "Default")
      (node (ref "STM32F407VGT6_DISCOVERY_BOARD") (pin "PC2") (pinfunction "PC2_PC2") (pintype "bidirectional"))
      (node (ref "STM32_PINKIRI") (pin "10") (pinfunction "10_10") (pintype "passive"))
    )
    (net (code "89") (name "Net-(STM32F407VGT6_DISCOVERY_BOARD-PadPC3)") (class "Default")
      (node (ref "STM32F407VGT6_DISCOVERY_BOARD") (pin "PC3") (pinfunction "PC3_PC3") (pintype "bidirectional"))
      (node (ref "STM32_PINKIRI") (pin "9") (pinfunction "9_9") (pintype "passive"))
    )
    (net (code "90") (name "Net-(STM32F407VGT6_DISCOVERY_BOARD-PadPC4)") (class "Default")
      (node (ref "STM32F407VGT6_DISCOVERY_BOARD") (pin "PC4") (pinfunction "PC4_PC4") (pintype "bidirectional"))
      (node (ref "STM32_PINKIRI") (pin "20") (pinfunction "20_20") (pintype "passive"))
    )
    (net (code "91") (name "Net-(STM32F407VGT6_DISCOVERY_BOARD-PadPC5)") (class "Default")
      (node (ref "STM32F407VGT6_DISCOVERY_BOARD") (pin "PC5") (pinfunction "PC5_PC5") (pintype "bidirectional"))
      (node (ref "STM32_PINKIRI") (pin "19") (pinfunction "19_19") (pintype "passive"))
    )
    (net (code "92") (name "Net-(STM32F407VGT6_DISCOVERY_BOARD-PadPC6)") (class "Default")
      (node (ref "STM32F407VGT6_DISCOVERY_BOARD") (pin "PC6") (pinfunction "PC6_PC6") (pintype "bidirectional"))
      (node (ref "STM32_PINKANAN") (pin "47") (pinfunction "47_47") (pintype "passive"))
    )
    (net (code "93") (name "Net-(STM32F407VGT6_DISCOVERY_BOARD-PadPC7)") (class "Default")
      (node (ref "STM32F407VGT6_DISCOVERY_BOARD") (pin "PC7") (pinfunction "PC7_PC7") (pintype "bidirectional"))
      (node (ref "STM32_PINKANAN") (pin "48") (pinfunction "48_48") (pintype "passive"))
    )
    (net (code "94") (name "Net-(STM32F407VGT6_DISCOVERY_BOARD-PadPC8)") (class "Default")
      (node (ref "STM32F407VGT6_DISCOVERY_BOARD") (pin "PC8") (pinfunction "PC8_PC8") (pintype "bidirectional"))
      (node (ref "STM32_PINKANAN") (pin "45") (pinfunction "45_45") (pintype "passive"))
    )
    (net (code "95") (name "Net-(STM32F407VGT6_DISCOVERY_BOARD-PadPC9)") (class "Default")
      (node (ref "STM32F407VGT6_DISCOVERY_BOARD") (pin "PC9") (pinfunction "PC9_PC9") (pintype "bidirectional"))
      (node (ref "STM32_PINKANAN") (pin "46") (pinfunction "46_46") (pintype "passive"))
    )
    (net (code "96") (name "Net-(STM32F407VGT6_DISCOVERY_BOARD-PadPC12)") (class "Default")
      (node (ref "STM32F407VGT6_DISCOVERY_BOARD") (pin "PC12") (pinfunction "PC12_PC12") (pintype "bidirectional"))
      (node (ref "STM32_PINKANAN") (pin "35") (pinfunction "35_35") (pintype "passive"))
    )
    (net (code "97") (name "Net-(STM32F407VGT6_DISCOVERY_BOARD-PadPC13)") (class "Default")
      (node (ref "STM32F407VGT6_DISCOVERY_BOARD") (pin "PC13") (pinfunction "PC13_PC13") (pintype "bidirectional"))
      (node (ref "STM32_PINKANAN") (pin "12") (pinfunction "12_12") (pintype "passive"))
    )
    (net (code "98") (name "Net-(STM32F407VGT6_DISCOVERY_BOARD-PadPC14)") (class "Default")
      (node (ref "STM32F407VGT6_DISCOVERY_BOARD") (pin "PC14") (pinfunction "PC14_PC14") (pintype "bidirectional"))
      (node (ref "STM32_PINKANAN") (pin "9") (pinfunction "9_9") (pintype "passive"))
    )
    (net (code "99") (name "Net-(STM32F407VGT6_DISCOVERY_BOARD-PadPC15)") (class "Default")
      (node (ref "STM32F407VGT6_DISCOVERY_BOARD") (pin "PC15") (pinfunction "PC15_PC15") (pintype "bidirectional"))
      (node (ref "STM32_PINKANAN") (pin "10") (pinfunction "10_10") (pintype "passive"))
    )
    (net (code "100") (name "Net-(STM32F407VGT6_DISCOVERY_BOARD-PadPD0)") (class "Default")
      (node (ref "STM32F407VGT6_DISCOVERY_BOARD") (pin "PD0") (pinfunction "PD0_PD0") (pintype "bidirectional"))
      (node (ref "STM32_PINKANAN") (pin "36") (pinfunction "36_36") (pintype "passive"))
    )
    (net (code "101") (name "Net-(STM32F407VGT6_DISCOVERY_BOARD-PadPD1)") (class "Default")
      (node (ref "STM32F407VGT6_DISCOVERY_BOARD") (pin "PD1") (pinfunction "PD1_PD1") (pintype "bidirectional"))
      (node (ref "STM32_PINKANAN") (pin "33") (pinfunction "33_33") (pintype "passive"))
    )
    (net (code "102") (name "Net-(STM32F407VGT6_DISCOVERY_BOARD-PadPD2)") (class "Default")
      (node (ref "STM32F407VGT6_DISCOVERY_BOARD") (pin "PD2") (pinfunction "PD2_PD2") (pintype "bidirectional"))
      (node (ref "STM32_PINKANAN") (pin "34") (pinfunction "34_34") (pintype "passive"))
    )
    (net (code "103") (name "Net-(STM32F407VGT6_DISCOVERY_BOARD-PadPD3)") (class "Default")
      (node (ref "STM32F407VGT6_DISCOVERY_BOARD") (pin "PD3") (pinfunction "PD3_PD3") (pintype "bidirectional"))
      (node (ref "STM32_PINKANAN") (pin "31") (pinfunction "31_31") (pintype "passive"))
    )
    (net (code "104") (name "Net-(STM32F407VGT6_DISCOVERY_BOARD-PadPD4)") (class "Default")
      (node (ref "STM32F407VGT6_DISCOVERY_BOARD") (pin "PD4") (pinfunction "PD4_PD4") (pintype "bidirectional"))
      (node (ref "STM32_PINKANAN") (pin "32") (pinfunction "32_32") (pintype "passive"))
    )
    (net (code "105") (name "Net-(STM32F407VGT6_DISCOVERY_BOARD-PadPD5)") (class "Default")
      (node (ref "STM32F407VGT6_DISCOVERY_BOARD") (pin "PD5") (pinfunction "PD5_PD5") (pintype "bidirectional"))
      (node (ref "STM32_PINKANAN") (pin "29") (pinfunction "29_29") (pintype "passive"))
    )
    (net (code "106") (name "Net-(STM32F407VGT6_DISCOVERY_BOARD-PadPD6)") (class "Default")
      (node (ref "STM32F407VGT6_DISCOVERY_BOARD") (pin "PD6") (pinfunction "PD6_PD6") (pintype "bidirectional"))
      (node (ref "STM32_PINKANAN") (pin "30") (pinfunction "30_30") (pintype "passive"))
    )
    (net (code "107") (name "Net-(STM32F407VGT6_DISCOVERY_BOARD-PadPD7)") (class "Default")
      (node (ref "STM32F407VGT6_DISCOVERY_BOARD") (pin "PD7") (pinfunction "PD7_PD7") (pintype "bidirectional"))
      (node (ref "STM32_PINKANAN") (pin "27") (pinfunction "27_27") (pintype "passive"))
    )
    (net (code "108") (name "Net-(STM32F407VGT6_DISCOVERY_BOARD-PadPD8)") (class "Default")
      (node (ref "STM32F407VGT6_DISCOVERY_BOARD") (pin "PD8") (pinfunction "PD8_PD8") (pintype "bidirectional"))
      (node (ref "STM32_PINKIRI") (pin "40") (pinfunction "40_40") (pintype "passive"))
    )
    (net (code "109") (name "Net-(STM32F407VGT6_DISCOVERY_BOARD-PadPD9)") (class "Default")
      (node (ref "STM32F407VGT6_DISCOVERY_BOARD") (pin "PD9") (pinfunction "PD9_PD9") (pintype "bidirectional"))
      (node (ref "STM32_PINKIRI") (pin "41") (pinfunction "41_41") (pintype "passive"))
    )
    (net (code "110") (name "Net-(STM32F407VGT6_DISCOVERY_BOARD-PadPD10)") (class "Default")
      (node (ref "STM32F407VGT6_DISCOVERY_BOARD") (pin "PD10") (pinfunction "PD10_PD10") (pintype "bidirectional"))
      (node (ref "STM32_PINKIRI") (pin "42") (pinfunction "42_42") (pintype "passive"))
    )
    (net (code "111") (name "Net-(STM32F407VGT6_DISCOVERY_BOARD-PadPD11)") (class "Default")
      (node (ref "STM32F407VGT6_DISCOVERY_BOARD") (pin "PD11") (pinfunction "PD11_PD11") (pintype "bidirectional"))
      (node (ref "STM32_PINKIRI") (pin "43") (pinfunction "43_43") (pintype "passive"))
    )
    (net (code "112") (name "Net-(STM32F407VGT6_DISCOVERY_BOARD-PadPD12)") (class "Default")
      (node (ref "STM32F407VGT6_DISCOVERY_BOARD") (pin "PD12") (pinfunction "PD12_PD12") (pintype "bidirectional"))
      (node (ref "STM32_PINKIRI") (pin "44") (pinfunction "44_44") (pintype "passive"))
    )
    (net (code "113") (name "Net-(STM32F407VGT6_DISCOVERY_BOARD-PadPD13)") (class "Default")
      (node (ref "STM32F407VGT6_DISCOVERY_BOARD") (pin "PD13") (pinfunction "PD13_PD13") (pintype "bidirectional"))
      (node (ref "STM32_PINKIRI") (pin "45") (pinfunction "45_45") (pintype "passive"))
    )
    (net (code "114") (name "Net-(STM32F407VGT6_DISCOVERY_BOARD-PadPD14)") (class "Default")
      (node (ref "STM32F407VGT6_DISCOVERY_BOARD") (pin "PD14") (pinfunction "PD14_PD14") (pintype "bidirectional"))
      (node (ref "STM32_PINKIRI") (pin "46") (pinfunction "46_46") (pintype "passive"))
    )
    (net (code "115") (name "Net-(STM32F407VGT6_DISCOVERY_BOARD-PadPD15)") (class "Default")
      (node (ref "STM32F407VGT6_DISCOVERY_BOARD") (pin "PD15") (pinfunction "PD15_PD15") (pintype "bidirectional"))
      (node (ref "STM32_PINKIRI") (pin "47") (pinfunction "47_47") (pintype "passive"))
    )
    (net (code "116") (name "Net-(STM32F407VGT6_DISCOVERY_BOARD-PadPE0)") (class "Default")
      (node (ref "STM32F407VGT6_DISCOVERY_BOARD") (pin "PE0") (pinfunction "PE0_PE0") (pintype "bidirectional"))
      (node (ref "STM32_PINKANAN") (pin "17") (pinfunction "17_17") (pintype "passive"))
    )
    (net (code "117") (name "Net-(STM32F407VGT6_DISCOVERY_BOARD-PadPE1)") (class "Default")
      (node (ref "STM32F407VGT6_DISCOVERY_BOARD") (pin "PE1") (pinfunction "PE1_PE1") (pintype "bidirectional"))
      (node (ref "STM32_PINKANAN") (pin "18") (pinfunction "18_18") (pintype "passive"))
    )
    (net (code "118") (name "Net-(STM32F407VGT6_DISCOVERY_BOARD-PadPE2)") (class "Default")
      (node (ref "STM32F407VGT6_DISCOVERY_BOARD") (pin "PE2") (pinfunction "PE2_PE2") (pintype "bidirectional"))
      (node (ref "STM32_PINKANAN") (pin "15") (pinfunction "15_15") (pintype "passive"))
    )
    (net (code "119") (name "Net-(STM32F407VGT6_DISCOVERY_BOARD-PadPE3)") (class "Default")
      (node (ref "STM32F407VGT6_DISCOVERY_BOARD") (pin "PE3") (pinfunction "PE3_PE3") (pintype "bidirectional"))
      (node (ref "STM32_PINKANAN") (pin "16") (pinfunction "16_16") (pintype "passive"))
    )
    (net (code "120") (name "Net-(STM32F407VGT6_DISCOVERY_BOARD-PadPE4)") (class "Default")
      (node (ref "STM32F407VGT6_DISCOVERY_BOARD") (pin "PE4") (pinfunction "PE4_PE4") (pintype "bidirectional"))
      (node (ref "STM32_PINKANAN") (pin "13") (pinfunction "13_13") (pintype "passive"))
    )
    (net (code "121") (name "Net-(STM32F407VGT6_DISCOVERY_BOARD-PadPE5)") (class "Default")
      (node (ref "STM32F407VGT6_DISCOVERY_BOARD") (pin "PE5") (pinfunction "PE5_PE5") (pintype "bidirectional"))
      (node (ref "STM32_PINKANAN") (pin "14") (pinfunction "14_14") (pintype "passive"))
    )
    (net (code "122") (name "Net-(STM32F407VGT6_DISCOVERY_BOARD-PadPE6)") (class "Default")
      (node (ref "STM32F407VGT6_DISCOVERY_BOARD") (pin "PE6") (pinfunction "PE6_PE6") (pintype "bidirectional"))
      (node (ref "STM32_PINKANAN") (pin "11") (pinfunction "11_11") (pintype "passive"))
    )
    (net (code "123") (name "Net-(STM32F407VGT6_DISCOVERY_BOARD-PadPE7)") (class "Default")
      (node (ref "STM32F407VGT6_DISCOVERY_BOARD") (pin "PE7") (pinfunction "PE7_PE7") (pintype "bidirectional"))
      (node (ref "STM32_PINKIRI") (pin "25") (pinfunction "25_25") (pintype "passive"))
    )
    (net (code "124") (name "Net-(STM32F407VGT6_DISCOVERY_BOARD-PadPE8)") (class "Default")
      (node (ref "STM32F407VGT6_DISCOVERY_BOARD") (pin "PE8") (pinfunction "PE8_PE8") (pintype "bidirectional"))
      (node (ref "STM32_PINKIRI") (pin "26") (pinfunction "26_26") (pintype "passive"))
    )
    (net (code "125") (name "Net-(STM32F407VGT6_DISCOVERY_BOARD-PadPE9)") (class "Default")
      (node (ref "STM32F407VGT6_DISCOVERY_BOARD") (pin "PE9") (pinfunction "PE9_PE9") (pintype "bidirectional"))
      (node (ref "STM32_PINKIRI") (pin "27") (pinfunction "27_27") (pintype "passive"))
    )
    (net (code "126") (name "Net-(STM32F407VGT6_DISCOVERY_BOARD-PadPE10)") (class "Default")
      (node (ref "STM32F407VGT6_DISCOVERY_BOARD") (pin "PE10") (pinfunction "PE10_PE10") (pintype "bidirectional"))
      (node (ref "STM32_PINKIRI") (pin "28") (pinfunction "28_28") (pintype "passive"))
    )
    (net (code "127") (name "Net-(STM32F407VGT6_DISCOVERY_BOARD-PadPE12)") (class "Default")
      (node (ref "STM32F407VGT6_DISCOVERY_BOARD") (pin "PE12") (pinfunction "PE12_PE12") (pintype "bidirectional"))
      (node (ref "STM32_PINKIRI") (pin "30") (pinfunction "30_30") (pintype "passive"))
    )
    (net (code "128") (name "Net-(STM32F407VGT6_DISCOVERY_BOARD-PadPE13)") (class "Default")
      (node (ref "STM32F407VGT6_DISCOVERY_BOARD") (pin "PE13") (pinfunction "PE13_PE13") (pintype "bidirectional"))
      (node (ref "STM32_PINKIRI") (pin "31") (pinfunction "31_31") (pintype "passive"))
    )
    (net (code "129") (name "Net-(STM32F407VGT6_DISCOVERY_BOARD-PadPE14)") (class "Default")
      (node (ref "STM32F407VGT6_DISCOVERY_BOARD") (pin "PE14") (pinfunction "PE14_PE14") (pintype "bidirectional"))
      (node (ref "STM32_PINKIRI") (pin "32") (pinfunction "32_32") (pintype "passive"))
    )
    (net (code "130") (name "Net-(STM32F407VGT6_DISCOVERY_BOARD-PadPE15)") (class "Default")
      (node (ref "STM32F407VGT6_DISCOVERY_BOARD") (pin "PE15") (pinfunction "PE15_PE15") (pintype "bidirectional"))
      (node (ref "STM32_PINKIRI") (pin "33") (pinfunction "33_33") (pintype "passive"))
    )
    (net (code "131") (name "Net-(STM32F407VGT6_DISCOVERY_BOARD-PadPH0)") (class "Default")
      (node (ref "STM32F407VGT6_DISCOVERY_BOARD") (pin "PH0") (pinfunction "PH0_PH0") (pintype "bidirectional"))
      (node (ref "STM32_PINKANAN") (pin "7") (pinfunction "7_7") (pintype "passive"))
    )
    (net (code "132") (name "Net-(STM32F407VGT6_DISCOVERY_BOARD-PadPH1)") (class "Default")
      (node (ref "STM32F407VGT6_DISCOVERY_BOARD") (pin "PH1") (pinfunction "PH1_PH1") (pintype "bidirectional"))
      (node (ref "STM32_PINKANAN") (pin "8") (pinfunction "8_8") (pintype "passive"))
    )
    (net (code "133") (name "Net-(STM32F407VGT6_DISCOVERY_BOARD-PadVDD)") (class "Default")
      (node (ref "STM32F407VGT6_DISCOVERY_BOARD") (pin "VDD") (pinfunction "VDD_VDD") (pintype "bidirectional"))
      (node (ref "STM32_PINKIRI") (pin "3") (pinfunction "3_3") (pintype "passive"))
    )
    (net (code "134") (name "Net-(STM32F407VGT6_DISCOVERY_BOARD-PadVDD2)") (class "Default")
      (node (ref "STM32F407VGT6_DISCOVERY_BOARD") (pin "VDD2") (pinfunction "VDD2_VDD2") (pintype "bidirectional"))
      (node (ref "STM32_PINKIRI") (pin "4") (pinfunction "4_4") (pintype "passive"))
    )
    (net (code "135") (name "Net-(STM32F407VGT6_DISCOVERY_BOARD-PadVDD3)") (class "Default")
      (node (ref "STM32F407VGT6_DISCOVERY_BOARD") (pin "VDD3") (pinfunction "VDD3_VDD3") (pintype "bidirectional"))
      (node (ref "STM32_PINKANAN") (pin "22") (pinfunction "22_22") (pintype "passive"))
    )
    (net (code "136") (name "Net-(T1-B)") (class "Default")
      (node (ref "R9") (pin "2") (pinfunction "2_2") (pintype "passive"))
      (node (ref "T1") (pin "2") (pinfunction "B_2") (pintype "passive"))
    )
    (net (code "137") (name "Net-(T1-C)") (class "Default")
      (node (ref "D3") (pin "A") (pinfunction "A_A") (pintype "passive"))
      (node (ref "K1") (pin "2") (pinfunction "2_2") (pintype "passive"))
      (node (ref "T1") (pin "3") (pinfunction "C_3") (pintype "passive"))
    )
    (net (code "138") (name "unconnected-(R12-PadE)") (class "Default")
      (node (ref "R12") (pin "E") (pinfunction "E_E") (pintype "passive"))
    )
    (net (code "139") (name "unconnected-(R13-PadE)") (class "Default")
      (node (ref "R13") (pin "E") (pinfunction "E_E") (pintype "passive"))
    )
    (net (code "140") (name "unconnected-(TM1-PadE)") (class "Default")
      (node (ref "TM1") (pin "E") (pinfunction "E_E") (pintype "passive"))
    )
    (net (code "141") (name "unconnected-(TM2-PadE)") (class "Default")
      (node (ref "TM2") (pin "E") (pinfunction "E_E") (pintype "passive"))
    )
  )
)
